# 1DDR3L_16bits.net
KiCad netlist of a schematic drawn in Altium Designer
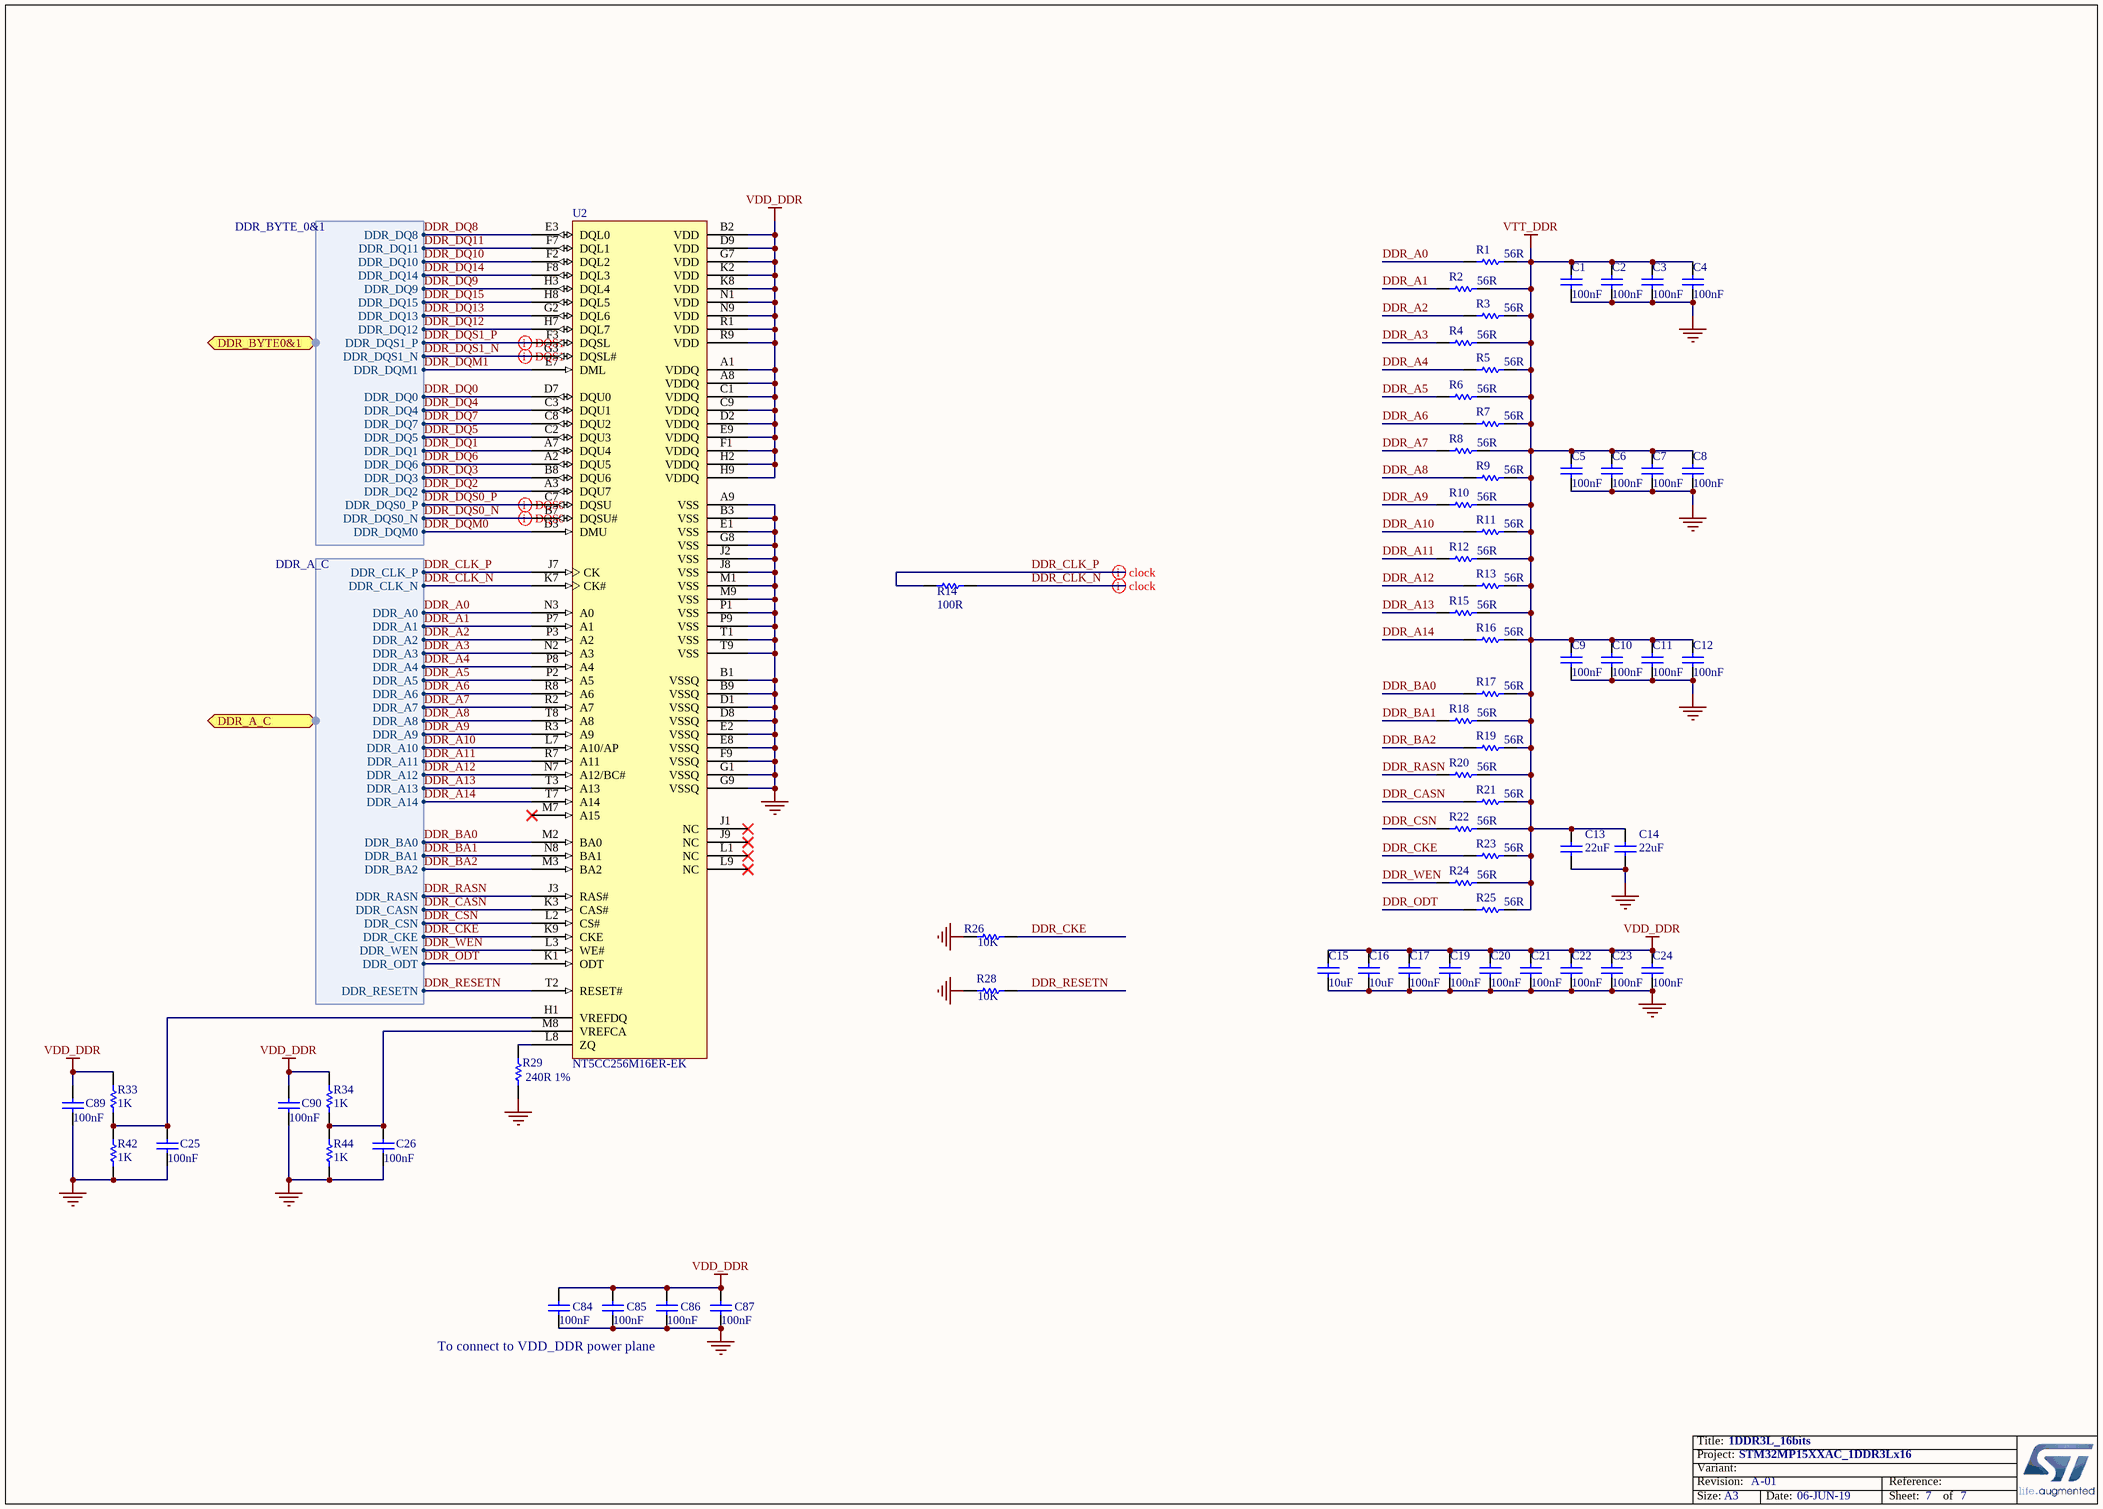
[diagram p0: 1DDR3L_16bits .SchDoc]

(export (version "E")
  (design (tool "Eeschema 10.0.6"))
  (components
    (comp (ref "C1")
      (value "100nF")
      (footprint "C0402")
      (description "Capacitor, MLCC, 100nF, 16V, X7R, 10%, 0402, T=0.5mm")
      (fields
        (field (name "INTERNAL_PART_NUMBER") "MCD-00006")
        (field (name "MANUFACTURER_PART_NUMBER") "CC0402KRX7R7BB104")
        (field (name "PROVIDED_BY") "SUBCO")
      )
      (libsource (lib "MCD_PARTS_database") (part "Capacitor"))
    )
    (comp (ref "C2")
      (value "100nF")
      (footprint "C0402")
      (description "Capacitor, MLCC, 100nF, 16V, X7R, 10%, 0402, T=0.5mm")
      (fields
        (field (name "INTERNAL_PART_NUMBER") "MCD-00006")
        (field (name "MANUFACTURER_PART_NUMBER") "CC0402KRX7R7BB104")
        (field (name "PROVIDED_BY") "SUBCO")
      )
      (libsource (lib "MCD_PARTS_database") (part "Capacitor"))
    )
    (comp (ref "C3")
      (value "100nF")
      (footprint "C0402")
      (description "Capacitor, MLCC, 100nF, 16V, X7R, 10%, 0402, T=0.5mm")
      (fields
        (field (name "INTERNAL_PART_NUMBER") "MCD-00006")
        (field (name "MANUFACTURER_PART_NUMBER") "CC0402KRX7R7BB104")
        (field (name "PROVIDED_BY") "SUBCO")
      )
      (libsource (lib "MCD_PARTS_database") (part "Capacitor"))
    )
    (comp (ref "C4")
      (value "100nF")
      (footprint "C0402")
      (description "Capacitor, MLCC, 100nF, 16V, X7R, 10%, 0402, T=0.5mm")
      (fields
        (field (name "INTERNAL_PART_NUMBER") "MCD-00006")
        (field (name "MANUFACTURER_PART_NUMBER") "CC0402KRX7R7BB104")
        (field (name "PROVIDED_BY") "SUBCO")
      )
      (libsource (lib "MCD_PARTS_database") (part "Capacitor"))
    )
    (comp (ref "C5")
      (value "100nF")
      (footprint "C0402")
      (description "Capacitor, MLCC, 100nF, 16V, X7R, 10%, 0402, T=0.5mm")
      (fields
        (field (name "INTERNAL_PART_NUMBER") "MCD-00006")
        (field (name "MANUFACTURER_PART_NUMBER") "CC0402KRX7R7BB104")
        (field (name "PROVIDED_BY") "SUBCO")
      )
      (libsource (lib "MCD_PARTS_database") (part "Capacitor"))
    )
    (comp (ref "C6")
      (value "100nF")
      (footprint "C0402")
      (description "Capacitor, MLCC, 100nF, 16V, X7R, 10%, 0402, T=0.5mm")
      (fields
        (field (name "INTERNAL_PART_NUMBER") "MCD-00006")
        (field (name "MANUFACTURER_PART_NUMBER") "CC0402KRX7R7BB104")
        (field (name "PROVIDED_BY") "SUBCO")
      )
      (libsource (lib "MCD_PARTS_database") (part "Capacitor"))
    )
    (comp (ref "C7")
      (value "100nF")
      (footprint "C0402")
      (description "Capacitor, MLCC, 100nF, 16V, X7R, 10%, 0402, T=0.5mm")
      (fields
        (field (name "INTERNAL_PART_NUMBER") "MCD-00006")
        (field (name "MANUFACTURER_PART_NUMBER") "CC0402KRX7R7BB104")
        (field (name "PROVIDED_BY") "SUBCO")
      )
      (libsource (lib "MCD_PARTS_database") (part "Capacitor"))
    )
    (comp (ref "C8")
      (value "100nF")
      (footprint "C0402")
      (description "Capacitor, MLCC, 100nF, 16V, X7R, 10%, 0402, T=0.5mm")
      (fields
        (field (name "INTERNAL_PART_NUMBER") "MCD-00006")
        (field (name "MANUFACTURER_PART_NUMBER") "CC0402KRX7R7BB104")
        (field (name "PROVIDED_BY") "SUBCO")
      )
      (libsource (lib "MCD_PARTS_database") (part "Capacitor"))
    )
    (comp (ref "C9")
      (value "100nF")
      (footprint "C0402")
      (description "Capacitor, MLCC, 100nF, 16V, X7R, 10%, 0402, T=0.5mm")
      (fields
        (field (name "INTERNAL_PART_NUMBER") "MCD-00006")
        (field (name "MANUFACTURER_PART_NUMBER") "CC0402KRX7R7BB104")
        (field (name "PROVIDED_BY") "SUBCO")
      )
      (libsource (lib "MCD_PARTS_database") (part "Capacitor"))
    )
    (comp (ref "C10")
      (value "100nF")
      (footprint "C0402")
      (description "Capacitor, MLCC, 100nF, 16V, X7R, 10%, 0402, T=0.5mm")
      (fields
        (field (name "INTERNAL_PART_NUMBER") "MCD-00006")
        (field (name "MANUFACTURER_PART_NUMBER") "CC0402KRX7R7BB104")
        (field (name "PROVIDED_BY") "SUBCO")
      )
      (libsource (lib "MCD_PARTS_database") (part "Capacitor"))
    )
    (comp (ref "C11")
      (value "100nF")
      (footprint "C0402")
      (description "Capacitor, MLCC, 100nF, 16V, X7R, 10%, 0402, T=0.5mm")
      (fields
        (field (name "INTERNAL_PART_NUMBER") "MCD-00006")
        (field (name "MANUFACTURER_PART_NUMBER") "CC0402KRX7R7BB104")
        (field (name "PROVIDED_BY") "SUBCO")
      )
      (libsource (lib "MCD_PARTS_database") (part "Capacitor"))
    )
    (comp (ref "C12")
      (value "100nF")
      (footprint "C0402")
      (description "Capacitor, MLCC, 100nF, 16V, X7R, 10%, 0402, T=0.5mm")
      (fields
        (field (name "INTERNAL_PART_NUMBER") "MCD-00006")
        (field (name "MANUFACTURER_PART_NUMBER") "CC0402KRX7R7BB104")
        (field (name "PROVIDED_BY") "SUBCO")
      )
      (libsource (lib "MCD_PARTS_database") (part "Capacitor"))
    )
    (comp (ref "C13")
      (value "22uF")
      (footprint "C0603")
      (description "Capacitor, MLCC, 22uF, 6V3, X5R, 20%, 0603, T=0,8mm")
      (fields
        (field (name "INTERNAL_PART_NUMBER") "MCD-00100")
        (field (name "MANUFACTURER_PART_NUMBER") "GRM188R60J226MEA0J")
        (field (name "PROVIDED_BY") "SUBCO")
      )
      (libsource (lib "MCD_PARTS_database") (part "Capacitor"))
    )
    (comp (ref "C14")
      (value "22uF")
      (footprint "C0603")
      (description "Capacitor, MLCC, 22uF, 6V3, X5R, 20%, 0603, T=0,8mm")
      (fields
        (field (name "INTERNAL_PART_NUMBER") "MCD-00100")
        (field (name "MANUFACTURER_PART_NUMBER") "GRM188R60J226MEA0J")
        (field (name "PROVIDED_BY") "SUBCO")
      )
      (libsource (lib "MCD_PARTS_database") (part "Capacitor"))
    )
    (comp (ref "C15")
      (value "10uF")
      (footprint "C0603")
      (description "Capacitor, MLCC, 10uF, 10V, X5R, 10%, 0603, T=0.8mm")
      (fields
        (field (name "INTERNAL_PART_NUMBER") "MCD-01124")
        (field (name "MANUFACTURER_PART_NUMBER") "GRM188R61A106KAAL")
        (field (name "PROVIDED_BY") "SUBCO")
      )
      (libsource (lib "MCD_PARTS_database") (part "Capacitor"))
    )
    (comp (ref "C16")
      (value "10uF")
      (footprint "C0603")
      (description "Capacitor, MLCC, 10uF, 10V, X5R, 10%, 0603, T=0.8mm")
      (fields
        (field (name "INTERNAL_PART_NUMBER") "MCD-01124")
        (field (name "MANUFACTURER_PART_NUMBER") "GRM188R61A106KAAL")
        (field (name "PROVIDED_BY") "SUBCO")
      )
      (libsource (lib "MCD_PARTS_database") (part "Capacitor"))
    )
    (comp (ref "C17")
      (value "100nF")
      (footprint "C0402")
      (description "Capacitor, MLCC, 100nF, 16V, X7R, 10%, 0402, T=0.5mm")
      (fields
        (field (name "INTERNAL_PART_NUMBER") "MCD-00006")
        (field (name "MANUFACTURER_PART_NUMBER") "CC0402KRX7R7BB104")
        (field (name "PROVIDED_BY") "SUBCO")
      )
      (libsource (lib "MCD_PARTS_database") (part "Capacitor"))
    )
    (comp (ref "C19")
      (value "100nF")
      (footprint "C0402")
      (description "Capacitor, MLCC, 100nF, 16V, X7R, 10%, 0402, T=0.5mm")
      (fields
        (field (name "INTERNAL_PART_NUMBER") "MCD-00006")
        (field (name "MANUFACTURER_PART_NUMBER") "CC0402KRX7R7BB104")
        (field (name "PROVIDED_BY") "SUBCO")
      )
      (libsource (lib "MCD_PARTS_database") (part "Capacitor"))
    )
    (comp (ref "C20")
      (value "100nF")
      (footprint "C0402")
      (description "Capacitor, MLCC, 100nF, 16V, X7R, 10%, 0402, T=0.5mm")
      (fields
        (field (name "INTERNAL_PART_NUMBER") "MCD-00006")
        (field (name "MANUFACTURER_PART_NUMBER") "CC0402KRX7R7BB104")
        (field (name "PROVIDED_BY") "SUBCO")
      )
      (libsource (lib "MCD_PARTS_database") (part "Capacitor"))
    )
    (comp (ref "C21")
      (value "100nF")
      (footprint "C0402")
      (description "Capacitor, MLCC, 100nF, 16V, X7R, 10%, 0402, T=0.5mm")
      (fields
        (field (name "INTERNAL_PART_NUMBER") "MCD-00006")
        (field (name "MANUFACTURER_PART_NUMBER") "CC0402KRX7R7BB104")
        (field (name "PROVIDED_BY") "SUBCO")
      )
      (libsource (lib "MCD_PARTS_database") (part "Capacitor"))
    )
    (comp (ref "C22")
      (value "100nF")
      (footprint "C0402")
      (description "Capacitor, MLCC, 100nF, 16V, X7R, 10%, 0402, T=0.5mm")
      (fields
        (field (name "INTERNAL_PART_NUMBER") "MCD-00006")
        (field (name "MANUFACTURER_PART_NUMBER") "CC0402KRX7R7BB104")
        (field (name "PROVIDED_BY") "SUBCO")
      )
      (libsource (lib "MCD_PARTS_database") (part "Capacitor"))
    )
    (comp (ref "C23")
      (value "100nF")
      (footprint "C0402")
      (description "Capacitor, MLCC, 100nF, 16V, X7R, 10%, 0402, T=0.5mm")
      (fields
        (field (name "INTERNAL_PART_NUMBER") "MCD-00006")
        (field (name "MANUFACTURER_PART_NUMBER") "CC0402KRX7R7BB104")
        (field (name "PROVIDED_BY") "SUBCO")
      )
      (libsource (lib "MCD_PARTS_database") (part "Capacitor"))
    )
    (comp (ref "C24")
      (value "100nF")
      (footprint "C0402")
      (description "Capacitor, MLCC, 100nF, 16V, X7R, 10%, 0402, T=0.5mm")
      (fields
        (field (name "INTERNAL_PART_NUMBER") "MCD-00006")
        (field (name "MANUFACTURER_PART_NUMBER") "CC0402KRX7R7BB104")
        (field (name "PROVIDED_BY") "SUBCO")
      )
      (libsource (lib "MCD_PARTS_database") (part "Capacitor"))
    )
    (comp (ref "C25")
      (value "100nF")
      (footprint "C0402")
      (description "Capacitor, MLCC, 100nF, 16V, X7R, 10%, 0402, T=0.5mm")
      (fields
        (field (name "INTERNAL_PART_NUMBER") "MCD-00006")
        (field (name "MANUFACTURER_PART_NUMBER") "CC0402KRX7R7BB104")
        (field (name "PROVIDED_BY") "SUBCO")
      )
      (libsource (lib "MCD_PARTS_database") (part "Capacitor"))
    )
    (comp (ref "C26")
      (value "100nF")
      (footprint "C0402")
      (description "Capacitor, MLCC, 100nF, 16V, X7R, 10%, 0402, T=0.5mm")
      (fields
        (field (name "INTERNAL_PART_NUMBER") "MCD-00006")
        (field (name "MANUFACTURER_PART_NUMBER") "CC0402KRX7R7BB104")
        (field (name "PROVIDED_BY") "SUBCO")
      )
      (libsource (lib "MCD_PARTS_database") (part "Capacitor"))
    )
    (comp (ref "C84")
      (value "100nF")
      (footprint "C0402")
      (description "Capacitor, MLCC, 100nF, 16V, X7R, 10%, 0402, T=0.5mm")
      (fields
        (field (name "INTERNAL_PART_NUMBER") "MCD-00006")
        (field (name "MANUFACTURER_PART_NUMBER") "CC0402KRX7R7BB104")
        (field (name "PROVIDED_BY") "SUBCO")
      )
      (libsource (lib "MCD_PARTS_database") (part "Capacitor"))
    )
    (comp (ref "C85")
      (value "100nF")
      (footprint "C0402")
      (description "Capacitor, MLCC, 100nF, 16V, X7R, 10%, 0402, T=0.5mm")
      (fields
        (field (name "INTERNAL_PART_NUMBER") "MCD-00006")
        (field (name "MANUFACTURER_PART_NUMBER") "CC0402KRX7R7BB104")
        (field (name "PROVIDED_BY") "SUBCO")
      )
      (libsource (lib "MCD_PARTS_database") (part "Capacitor"))
    )
    (comp (ref "C86")
      (value "100nF")
      (footprint "C0402")
      (description "Capacitor, MLCC, 100nF, 16V, X7R, 10%, 0402, T=0.5mm")
      (fields
        (field (name "INTERNAL_PART_NUMBER") "MCD-00006")
        (field (name "MANUFACTURER_PART_NUMBER") "CC0402KRX7R7BB104")
        (field (name "PROVIDED_BY") "SUBCO")
      )
      (libsource (lib "MCD_PARTS_database") (part "Capacitor"))
    )
    (comp (ref "C87")
      (value "100nF")
      (footprint "C0402")
      (description "Capacitor, MLCC, 100nF, 16V, X7R, 10%, 0402, T=0.5mm")
      (fields
        (field (name "INTERNAL_PART_NUMBER") "MCD-00006")
        (field (name "MANUFACTURER_PART_NUMBER") "CC0402KRX7R7BB104")
        (field (name "PROVIDED_BY") "SUBCO")
      )
      (libsource (lib "MCD_PARTS_database") (part "Capacitor"))
    )
    (comp (ref "C89")
      (value "100nF")
      (footprint "C0402")
      (description "Capacitor, MLCC, 100nF, 16V, X7R, 10%, 0402, T=0.5mm")
      (fields
        (field (name "INTERNAL_PART_NUMBER") "MCD-00006")
        (field (name "MANUFACTURER_PART_NUMBER") "CC0402KRX7R7BB104")
        (field (name "PROVIDED_BY") "SUBCO")
      )
      (libsource (lib "MCD_PARTS_database") (part "Capacitor"))
    )
    (comp (ref "C90")
      (value "100nF")
      (footprint "C0402")
      (description "Capacitor, MLCC, 100nF, 16V, X7R, 10%, 0402, T=0.5mm")
      (fields
        (field (name "INTERNAL_PART_NUMBER") "MCD-00006")
        (field (name "MANUFACTURER_PART_NUMBER") "CC0402KRX7R7BB104")
        (field (name "PROVIDED_BY") "SUBCO")
      )
      (libsource (lib "MCD_PARTS_database") (part "Capacitor"))
    )
    (comp (ref "R1")
      (value "56R")
      (footprint "R0402")
      (description "Resistor,56R,0402,1%,1/16W")
      (fields
        (field (name "INTERNAL_PART_NUMBER") "MCD-00054")
        (field (name "MANUFACTURER_PART_NUMBER") "RC0402FR-0756RL")
        (field (name "PROVIDED_BY") "SUBCO")
      )
      (libsource (lib "MCD_PARTS_database") (part "Resistor"))
    )
    (comp (ref "R2")
      (value "56R")
      (footprint "R0402")
      (description "Resistor,56R,0402,1%,1/16W")
      (fields
        (field (name "INTERNAL_PART_NUMBER") "MCD-00054")
        (field (name "MANUFACTURER_PART_NUMBER") "RC0402FR-0756RL")
        (field (name "PROVIDED_BY") "SUBCO")
      )
      (libsource (lib "MCD_PARTS_database") (part "Resistor"))
    )
    (comp (ref "R3")
      (value "56R")
      (footprint "R0402")
      (description "Resistor,56R,0402,1%,1/16W")
      (fields
        (field (name "INTERNAL_PART_NUMBER") "MCD-00054")
        (field (name "MANUFACTURER_PART_NUMBER") "RC0402FR-0756RL")
        (field (name "PROVIDED_BY") "SUBCO")
      )
      (libsource (lib "MCD_PARTS_database") (part "Resistor"))
    )
    (comp (ref "R4")
      (value "56R")
      (footprint "R0402")
      (description "Resistor,56R,0402,1%,1/16W")
      (fields
        (field (name "INTERNAL_PART_NUMBER") "MCD-00054")
        (field (name "MANUFACTURER_PART_NUMBER") "RC0402FR-0756RL")
        (field (name "PROVIDED_BY") "SUBCO")
      )
      (libsource (lib "MCD_PARTS_database") (part "Resistor"))
    )
    (comp (ref "R5")
      (value "56R")
      (footprint "R0402")
      (description "Resistor,56R,0402,1%,1/16W")
      (fields
        (field (name "INTERNAL_PART_NUMBER") "MCD-00054")
        (field (name "MANUFACTURER_PART_NUMBER") "RC0402FR-0756RL")
        (field (name "PROVIDED_BY") "SUBCO")
      )
      (libsource (lib "MCD_PARTS_database") (part "Resistor"))
    )
    (comp (ref "R6")
      (value "56R")
      (footprint "R0402")
      (description "Resistor,56R,0402,1%,1/16W")
      (fields
        (field (name "INTERNAL_PART_NUMBER") "MCD-00054")
        (field (name "MANUFACTURER_PART_NUMBER") "RC0402FR-0756RL")
        (field (name "PROVIDED_BY") "SUBCO")
      )
      (libsource (lib "MCD_PARTS_database") (part "Resistor"))
    )
    (comp (ref "R7")
      (value "56R")
      (footprint "R0402")
      (description "Resistor,56R,0402,1%,1/16W")
      (fields
        (field (name "INTERNAL_PART_NUMBER") "MCD-00054")
        (field (name "MANUFACTURER_PART_NUMBER") "RC0402FR-0756RL")
        (field (name "PROVIDED_BY") "SUBCO")
      )
      (libsource (lib "MCD_PARTS_database") (part "Resistor"))
    )
    (comp (ref "R8")
      (value "56R")
      (footprint "R0402")
      (description "Resistor,56R,0402,1%,1/16W")
      (fields
        (field (name "INTERNAL_PART_NUMBER") "MCD-00054")
        (field (name "MANUFACTURER_PART_NUMBER") "RC0402FR-0756RL")
        (field (name "PROVIDED_BY") "SUBCO")
      )
      (libsource (lib "MCD_PARTS_database") (part "Resistor"))
    )
    (comp (ref "R9")
      (value "56R")
      (footprint "R0402")
      (description "Resistor,56R,0402,1%,1/16W")
      (fields
        (field (name "INTERNAL_PART_NUMBER") "MCD-00054")
        (field (name "MANUFACTURER_PART_NUMBER") "RC0402FR-0756RL")
        (field (name "PROVIDED_BY") "SUBCO")
      )
      (libsource (lib "MCD_PARTS_database") (part "Resistor"))
    )
    (comp (ref "R10")
      (value "56R")
      (footprint "R0402")
      (description "Resistor,56R,0402,1%,1/16W")
      (fields
        (field (name "INTERNAL_PART_NUMBER") "MCD-00054")
        (field (name "MANUFACTURER_PART_NUMBER") "RC0402FR-0756RL")
        (field (name "PROVIDED_BY") "SUBCO")
      )
      (libsource (lib "MCD_PARTS_database") (part "Resistor"))
    )
    (comp (ref "R11")
      (value "56R")
      (footprint "R0402")
      (description "Resistor,56R,0402,1%,1/16W")
      (fields
        (field (name "INTERNAL_PART_NUMBER") "MCD-00054")
        (field (name "MANUFACTURER_PART_NUMBER") "RC0402FR-0756RL")
        (field (name "PROVIDED_BY") "SUBCO")
      )
      (libsource (lib "MCD_PARTS_database") (part "Resistor"))
    )
    (comp (ref "R12")
      (value "56R")
      (footprint "R0402")
      (description "Resistor,56R,0402,1%,1/16W")
      (fields
        (field (name "INTERNAL_PART_NUMBER") "MCD-00054")
        (field (name "MANUFACTURER_PART_NUMBER") "RC0402FR-0756RL")
        (field (name "PROVIDED_BY") "SUBCO")
      )
      (libsource (lib "MCD_PARTS_database") (part "Resistor"))
    )
    (comp (ref "R13")
      (value "56R")
      (footprint "R0402")
      (description "Resistor,56R,0402,1%,1/16W")
      (fields
        (field (name "INTERNAL_PART_NUMBER") "MCD-00054")
        (field (name "MANUFACTURER_PART_NUMBER") "RC0402FR-0756RL")
        (field (name "PROVIDED_BY") "SUBCO")
      )
      (libsource (lib "MCD_PARTS_database") (part "Resistor"))
    )
    (comp (ref "R14")
      (value "100R")
      (footprint "R0402")
      (description "Resistor,100R,0402,1%,1/16W")
      (fields
        (field (name "INTERNAL_PART_NUMBER") "MCD-00067")
        (field (name "MANUFACTURER_PART_NUMBER") "RC0402FR-07100RL")
        (field (name "PROVIDED_BY") "SUBCO")
      )
      (libsource (lib "MCD_PARTS_database") (part "Resistor"))
    )
    (comp (ref "R15")
      (value "56R")
      (footprint "R0402")
      (description "Resistor,56R,0402,1%,1/16W")
      (fields
        (field (name "INTERNAL_PART_NUMBER") "MCD-00054")
        (field (name "MANUFACTURER_PART_NUMBER") "RC0402FR-0756RL")
        (field (name "PROVIDED_BY") "SUBCO")
      )
      (libsource (lib "MCD_PARTS_database") (part "Resistor"))
    )
    (comp (ref "R16")
      (value "56R")
      (footprint "R0402")
      (description "Resistor,56R,0402,1%,1/16W")
      (fields
        (field (name "INTERNAL_PART_NUMBER") "MCD-00054")
        (field (name "MANUFACTURER_PART_NUMBER") "RC0402FR-0756RL")
        (field (name "PROVIDED_BY") "SUBCO")
      )
      (libsource (lib "MCD_PARTS_database") (part "Resistor"))
    )
    (comp (ref "R17")
      (value "56R")
      (footprint "R0402")
      (description "Resistor,56R,0402,1%,1/16W")
      (fields
        (field (name "INTERNAL_PART_NUMBER") "MCD-00054")
        (field (name "MANUFACTURER_PART_NUMBER") "RC0402FR-0756RL")
        (field (name "PROVIDED_BY") "SUBCO")
      )
      (libsource (lib "MCD_PARTS_database") (part "Resistor"))
    )
    (comp (ref "R18")
      (value "56R")
      (footprint "R0402")
      (description "Resistor,56R,0402,1%,1/16W")
      (fields
        (field (name "INTERNAL_PART_NUMBER") "MCD-00054")
        (field (name "MANUFACTURER_PART_NUMBER") "RC0402FR-0756RL")
        (field (name "PROVIDED_BY") "SUBCO")
      )
      (libsource (lib "MCD_PARTS_database") (part "Resistor"))
    )
    (comp (ref "R19")
      (value "56R")
      (footprint "R0402")
      (description "Resistor,56R,0402,1%,1/16W")
      (fields
        (field (name "INTERNAL_PART_NUMBER") "MCD-00054")
        (field (name "MANUFACTURER_PART_NUMBER") "RC0402FR-0756RL")
        (field (name "PROVIDED_BY") "SUBCO")
      )
      (libsource (lib "MCD_PARTS_database") (part "Resistor"))
    )
    (comp (ref "R20")
      (value "56R")
      (footprint "R0402")
      (description "Resistor,56R,0402,1%,1/16W")
      (fields
        (field (name "INTERNAL_PART_NUMBER") "MCD-00054")
        (field (name "MANUFACTURER_PART_NUMBER") "RC0402FR-0756RL")
        (field (name "PROVIDED_BY") "SUBCO")
      )
      (libsource (lib "MCD_PARTS_database") (part "Resistor"))
    )
    (comp (ref "R21")
      (value "56R")
      (footprint "R0402")
      (description "Resistor,56R,0402,1%,1/16W")
      (fields
        (field (name "INTERNAL_PART_NUMBER") "MCD-00054")
        (field (name "MANUFACTURER_PART_NUMBER") "RC0402FR-0756RL")
        (field (name "PROVIDED_BY") "SUBCO")
      )
      (libsource (lib "MCD_PARTS_database") (part "Resistor"))
    )
    (comp (ref "R22")
      (value "56R")
      (footprint "R0402")
      (description "Resistor,56R,0402,1%,1/16W")
      (fields
        (field (name "INTERNAL_PART_NUMBER") "MCD-00054")
        (field (name "MANUFACTURER_PART_NUMBER") "RC0402FR-0756RL")
        (field (name "PROVIDED_BY") "SUBCO")
      )
      (libsource (lib "MCD_PARTS_database") (part "Resistor"))
    )
    (comp (ref "R23")
      (value "56R")
      (footprint "R0402")
      (description "Resistor,56R,0402,1%,1/16W")
      (fields
        (field (name "INTERNAL_PART_NUMBER") "MCD-00054")
        (field (name "MANUFACTURER_PART_NUMBER") "RC0402FR-0756RL")
        (field (name "PROVIDED_BY") "SUBCO")
      )
      (libsource (lib "MCD_PARTS_database") (part "Resistor"))
    )
    (comp (ref "R24")
      (value "56R")
      (footprint "R0402")
      (description "Resistor,56R,0402,1%,1/16W")
      (fields
        (field (name "INTERNAL_PART_NUMBER") "MCD-00054")
        (field (name "MANUFACTURER_PART_NUMBER") "RC0402FR-0756RL")
        (field (name "PROVIDED_BY") "SUBCO")
      )
      (libsource (lib "MCD_PARTS_database") (part "Resistor"))
    )
    (comp (ref "R25")
      (value "56R")
      (footprint "R0402")
      (description "Resistor,56R,0402,1%,1/16W")
      (fields
        (field (name "INTERNAL_PART_NUMBER") "MCD-00054")
        (field (name "MANUFACTURER_PART_NUMBER") "RC0402FR-0756RL")
        (field (name "PROVIDED_BY") "SUBCO")
      )
      (libsource (lib "MCD_PARTS_database") (part "Resistor"))
    )
    (comp (ref "R26")
      (value "10K")
      (footprint "R0402")
      (description "Resistor,10K,0402,1%,1/16W")
      (fields
        (field (name "INTERNAL_PART_NUMBER") "MCD-00053")
        (field (name "MANUFACTURER_PART_NUMBER") "RC0402FR-0710KL")
        (field (name "PROVIDED_BY") "SUBCO")
      )
      (libsource (lib "MCD_PARTS_database") (part "Resistor"))
    )
    (comp (ref "R28")
      (value "10K")
      (footprint "R0402")
      (description "Resistor,10K,0402,1%,1/16W")
      (fields
        (field (name "INTERNAL_PART_NUMBER") "MCD-00053")
        (field (name "MANUFACTURER_PART_NUMBER") "RC0402FR-0710KL")
        (field (name "PROVIDED_BY") "SUBCO")
      )
      (libsource (lib "MCD_PARTS_database") (part "Resistor"))
    )
    (comp (ref "R29")
      (value "240R 1%")
      (footprint "R0402")
      (description "Resistor,240R,0402,1%,1/16W")
      (fields
        (field (name "INTERNAL_PART_NUMBER") "MCD-00120")
        (field (name "MANUFACTURER_PART_NUMBER") "RC0402FR-07240RL")
        (field (name "PROVIDED_BY") "SUBCO")
      )
      (libsource (lib "MCD_PARTS_database") (part "Resistor"))
    )
    (comp (ref "R33")
      (value "1K")
      (footprint "R0402")
      (description "Resistor,1K,0402,1%,1/16W")
      (fields
        (field (name "INTERNAL_PART_NUMBER") "MCD-00061")
        (field (name "MANUFACTURER_PART_NUMBER") "RC0402FR-071KL")
        (field (name "PROVIDED_BY") "SUBCO")
      )
      (libsource (lib "MCD_PARTS_database") (part "Resistor"))
    )
    (comp (ref "R34")
      (value "1K")
      (footprint "R0402")
      (description "Resistor,1K,0402,1%,1/16W")
      (fields
        (field (name "INTERNAL_PART_NUMBER") "MCD-00061")
        (field (name "MANUFACTURER_PART_NUMBER") "RC0402FR-071KL")
        (field (name "PROVIDED_BY") "SUBCO")
      )
      (libsource (lib "MCD_PARTS_database") (part "Resistor"))
    )
    (comp (ref "R42")
      (value "1K")
      (footprint "R0402")
      (description "Resistor,1K,0402,1%,1/16W")
      (fields
        (field (name "INTERNAL_PART_NUMBER") "MCD-00061")
        (field (name "MANUFACTURER_PART_NUMBER") "RC0402FR-071KL")
        (field (name "PROVIDED_BY") "SUBCO")
      )
      (libsource (lib "MCD_PARTS_database") (part "Resistor"))
    )
    (comp (ref "R44")
      (value "1K")
      (footprint "R0402")
      (description "Resistor,1K,0402,1%,1/16W")
      (fields
        (field (name "INTERNAL_PART_NUMBER") "MCD-00061")
        (field (name "MANUFACTURER_PART_NUMBER") "RC0402FR-071KL")
        (field (name "PROVIDED_BY") "SUBCO")
      )
      (libsource (lib "MCD_PARTS_database") (part "Resistor"))
    )
    (comp (ref "U2")
      (value "NT5CC256M16ER-EK")
      (footprint "ICC_VFBGA96_9x13_P080")
      (description "Memory,DDR3L,4Gb,256Mbx16,933Mhz,1V35,TFBGA")
      (fields
        (field (name "INTERNAL_PART_NUMBER") "MCD-01811")
        (field (name "MANUFACTURER") "NANYA")
        (field (name "PROVIDED_BY") "SUBCO")
      )
      (libsource (lib "MCD_PARTS_database") (part "NT5CC256M16ER-EK"))
    )
  )
  (nets
    (net (code "3") (name "/DDR_A0") (class "Default")
      (node (ref "R1") (pin "1") (pinfunction "1_1") (pintype "passive"))
      (node (ref "U2") (pin "N3") (pinfunction "A0_N3") (pintype "input"))
    )
    (net (code "4") (name "/DDR_A1") (class "Default")
      (node (ref "R2") (pin "1") (pinfunction "1_1") (pintype "passive"))
      (node (ref "U2") (pin "P7") (pinfunction "A1_P7") (pintype "input"))
    )
    (net (code "5") (name "/DDR_A2") (class "Default")
      (node (ref "R3") (pin "1") (pinfunction "1_1") (pintype "passive"))
      (node (ref "U2") (pin "P3") (pinfunction "A2_P3") (pintype "input"))
    )
    (net (code "6") (name "/DDR_A3") (class "Default")
      (node (ref "R4") (pin "1") (pinfunction "1_1") (pintype "passive"))
      (node (ref "U2") (pin "N2") (pinfunction "A3_N2") (pintype "input"))
    )
    (net (code "7") (name "/DDR_A4") (class "Default")
      (node (ref "R5") (pin "1") (pinfunction "1_1") (pintype "passive"))
      (node (ref "U2") (pin "P8") (pinfunction "A4_P8") (pintype "input"))
    )
    (net (code "8") (name "/DDR_A5") (class "Default")
      (node (ref "R6") (pin "1") (pinfunction "1_1") (pintype "passive"))
      (node (ref "U2") (pin "P2") (pinfunction "A5_P2") (pintype "input"))
    )
    (net (code "9") (name "/DDR_A6") (class "Default")
      (node (ref "R7") (pin "1") (pinfunction "1_1") (pintype "passive"))
      (node (ref "U2") (pin "R8") (pinfunction "A6_R8") (pintype "input"))
    )
    (net (code "10") (name "/DDR_A7") (class "Default")
      (node (ref "R8") (pin "1") (pinfunction "1_1") (pintype "passive"))
      (node (ref "U2") (pin "R2") (pinfunction "A7_R2") (pintype "input"))
    )
    (net (code "11") (name "/DDR_A8") (class "Default")
      (node (ref "R9") (pin "1") (pinfunction "1_1") (pintype "passive"))
      (node (ref "U2") (pin "T8") (pinfunction "A8_T8") (pintype "input"))
    )
    (net (code "12") (name "/DDR_A9") (class "Default")
      (node (ref "R10") (pin "1") (pinfunction "1_1") (pintype "passive"))
      (node (ref "U2") (pin "R3") (pinfunction "A9_R3") (pintype "input"))
    )
    (net (code "13") (name "/DDR_A10") (class "Default")
      (node (ref "R11") (pin "1") (pinfunction "1_1") (pintype "passive"))
      (node (ref "U2") (pin "L7") (pinfunction "A10/AP_L7") (pintype "input"))
    )
    (net (code "14") (name "/DDR_A11") (class "Default")
      (node (ref "R12") (pin "1") (pinfunction "1_1") (pintype "passive"))
      (node (ref "U2") (pin "R7") (pinfunction "A11_R7") (pintype "input"))
    )
    (net (code "15") (name "/DDR_A12") (class "Default")
      (node (ref "R13") (pin "1") (pinfunction "1_1") (pintype "passive"))
      (node (ref "U2") (pin "N7") (pinfunction "A12/BC#_N7") (pintype "input"))
    )
    (net (code "16") (name "/DDR_A13") (class "Default")
      (node (ref "R15") (pin "1") (pinfunction "1_1") (pintype "passive"))
      (node (ref "U2") (pin "T3") (pinfunction "A13_T3") (pintype "input"))
    )
    (net (code "17") (name "/DDR_A14") (class "Default")
      (node (ref "R16") (pin "1") (pinfunction "1_1") (pintype "passive"))
      (node (ref "U2") (pin "T7") (pinfunction "A14_T7") (pintype "input"))
    )
    (net (code "18") (name "/DDR_BA0") (class "Default")
      (node (ref "R17") (pin "1") (pinfunction "1_1") (pintype "passive"))
      (node (ref "U2") (pin "M2") (pinfunction "BA0_M2") (pintype "input"))
    )
    (net (code "19") (name "/DDR_BA1") (class "Default")
      (node (ref "R18") (pin "1") (pinfunction "1_1") (pintype "passive"))
      (node (ref "U2") (pin "N8") (pinfunction "BA1_N8") (pintype "input"))
    )
    (net (code "20") (name "/DDR_BA2") (class "Default")
      (node (ref "R19") (pin "1") (pinfunction "1_1") (pintype "passive"))
      (node (ref "U2") (pin "M3") (pinfunction "BA2_M3") (pintype "input"))
    )
    (net (code "21") (name "/DDR_CASN") (class "Default")
      (node (ref "R21") (pin "1") (pinfunction "1_1") (pintype "passive"))
      (node (ref "U2") (pin "K3") (pinfunction "CAS#_K3") (pintype "input"))
    )
    (net (code "22") (name "/DDR_CKE") (class "Default")
      (node (ref "R23") (pin "1") (pinfunction "1_1") (pintype "passive"))
      (node (ref "R26") (pin "2") (pinfunction "2_2") (pintype "passive"))
      (node (ref "U2") (pin "K9") (pinfunction "CKE_K9") (pintype "input"))
    )
    (net (code "23") (name "/DDR_CLK_N") (class "Default")
      (node (ref "R14") (pin "2") (pinfunction "2_2") (pintype "passive"))
      (node (ref "U2") (pin "K7") (pinfunction "CK#_K7") (pintype "input"))
    )
    (net (code "24") (name "/DDR_CLK_P") (class "Default")
      (node (ref "R14") (pin "1") (pinfunction "1_1") (pintype "passive"))
      (node (ref "U2") (pin "J7") (pinfunction "CK_J7") (pintype "input"))
    )
    (net (code "25") (name "/DDR_CSN") (class "Default")
      (node (ref "R22") (pin "1") (pinfunction "1_1") (pintype "passive"))
      (node (ref "U2") (pin "L2") (pinfunction "CS#_L2") (pintype "input"))
    )
    (net (code "26") (name "/DDR_DQ0") (class "Default")
      (node (ref "U2") (pin "D7") (pinfunction "DQU0_D7") (pintype "bidirectional"))
    )
    (net (code "27") (name "/DDR_DQ1") (class "Default")
      (node (ref "U2") (pin "A7") (pinfunction "DQU4_A7") (pintype "bidirectional"))
    )
    (net (code "28") (name "/DDR_DQ2") (class "Default")
      (node (ref "U2") (pin "A3") (pinfunction "DQU7_A3") (pintype "bidirectional"))
    )
    (net (code "29") (name "/DDR_DQ3") (class "Default")
      (node (ref "U2") (pin "B8") (pinfunction "DQU6_B8") (pintype "bidirectional"))
    )
    (net (code "30") (name "/DDR_DQ4") (class "Default")
      (node (ref "U2") (pin "C3") (pinfunction "DQU1_C3") (pintype "bidirectional"))
    )
    (net (code "31") (name "/DDR_DQ5") (class "Default")
      (node (ref "U2") (pin "C2") (pinfunction "DQU3_C2") (pintype "bidirectional"))
    )
    (net (code "32") (name "/DDR_DQ6") (class "Default")
      (node (ref "U2") (pin "A2") (pinfunction "DQU5_A2") (pintype "bidirectional"))
    )
    (net (code "33") (name "/DDR_DQ7") (class "Default")
      (node (ref "U2") (pin "C8") (pinfunction "DQU2_C8") (pintype "bidirectional"))
    )
    (net (code "34") (name "/DDR_DQ8") (class "Default")
      (node (ref "U2") (pin "E3") (pinfunction "DQL0_E3") (pintype "bidirectional"))
    )
    (net (code "35") (name "/DDR_DQ9") (class "Default")
      (node (ref "U2") (pin "H3") (pinfunction "DQL4_H3") (pintype "bidirectional"))
    )
    (net (code "36") (name "/DDR_DQ10") (class "Default")
      (node (ref "U2") (pin "F2") (pinfunction "DQL2_F2") (pintype "bidirectional"))
    )
    (net (code "37") (name "/DDR_DQ11") (class "Default")
      (node (ref "U2") (pin "F7") (pinfunction "DQL1_F7") (pintype "bidirectional"))
    )
    (net (code "38") (name "/DDR_DQ12") (class "Default")
      (node (ref "U2") (pin "H7") (pinfunction "DQL7_H7") (pintype "bidirectional"))
    )
    (net (code "39") (name "/DDR_DQ13") (class "Default")
      (node (ref "U2") (pin "G2") (pinfunction "DQL6_G2") (pintype "bidirectional"))
    )
    (net (code "40") (name "/DDR_DQ14") (class "Default")
      (node (ref "U2") (pin "F8") (pinfunction "DQL3_F8") (pintype "bidirectional"))
    )
    (net (code "41") (name "/DDR_DQ15") (class "Default")
      (node (ref "U2") (pin "H8") (pinfunction "DQL5_H8") (pintype "bidirectional"))
    )
    (net (code "42") (name "/DDR_DQM0") (class "Default")
      (node (ref "U2") (pin "D3") (pinfunction "DMU_D3") (pintype "input"))
    )
    (net (code "43") (name "/DDR_DQM1") (class "Default")
      (node (ref "U2") (pin "E7") (pinfunction "DML_E7") (pintype "input"))
    )
    (net (code "44") (name "/DDR_DQS0_N") (class "Default")
      (node (ref "U2") (pin "B7") (pinfunction "DQSU#_B7") (pintype "bidirectional"))
    )
    (net (code "45") (name "/DDR_DQS0_P") (class "Default")
      (node (ref "U2") (pin "C7") (pinfunction "DQSU_C7") (pintype "bidirectional"))
    )
    (net (code "46") (name "/DDR_DQS1_N") (class "Default")
      (node (ref "U2") (pin "G3") (pinfunction "DQSL#_G3") (pintype "bidirectional"))
    )
    (net (code "47") (name "/DDR_DQS1_P") (class "Default")
      (node (ref "U2") (pin "F3") (pinfunction "DQSL_F3") (pintype "bidirectional"))
    )
    (net (code "48") (name "/DDR_ODT") (class "Default")
      (node (ref "R25") (pin "1") (pinfunction "1_1") (pintype "passive"))
      (node (ref "U2") (pin "K1") (pinfunction "ODT_K1") (pintype "input"))
    )
    (net (code "49") (name "/DDR_RASN") (class "Default")
      (node (ref "R20") (pin "1") (pinfunction "1_1") (pintype "passive"))
      (node (ref "U2") (pin "J3") (pinfunction "RAS#_J3") (pintype "input"))
    )
    (net (code "50") (name "/DDR_RESETN") (class "Default")
      (node (ref "R28") (pin "2") (pinfunction "2_2") (pintype "passive"))
      (node (ref "U2") (pin "T2") (pinfunction "RESET#_T2") (pintype "input"))
    )
    (net (code "51") (name "/DDR_WEN") (class "Default")
      (node (ref "R24") (pin "1") (pinfunction "1_1") (pintype "passive"))
      (node (ref "U2") (pin "L3") (pinfunction "WE#_L3") (pintype "input"))
    )
    (net (code "54") (name "GND") (class "Default")
      (node (ref "C1") (pin "2") (pinfunction "2_2") (pintype "passive"))
      (node (ref "C10") (pin "2") (pinfunction "2_2") (pintype "passive"))
      (node (ref "C11") (pin "2") (pinfunction "2_2") (pintype "passive"))
      (node (ref "C12") (pin "2") (pinfunction "2_2") (pintype "passive"))
      (node (ref "C13") (pin "1") (pinfunction "1_1") (pintype "passive"))
      (node (ref "C14") (pin "1") (pinfunction "1_1") (pintype "passive"))
      (node (ref "C15") (pin "1") (pinfunction "1_1") (pintype "passive"))
      (node (ref "C16") (pin "1") (pinfunction "1_1") (pintype "passive"))
      (node (ref "C17") (pin "2") (pinfunction "2_2") (pintype "passive"))
      (node (ref "C19") (pin "2") (pinfunction "2_2") (pintype "passive"))
      (node (ref "C2") (pin "2") (pinfunction "2_2") (pintype "passive"))
      (node (ref "C20") (pin "2") (pinfunction "2_2") (pintype "passive"))
      (node (ref "C21") (pin "2") (pinfunction "2_2") (pintype "passive"))
      (node (ref "C22") (pin "2") (pinfunction "2_2") (pintype "passive"))
      (node (ref "C23") (pin "2") (pinfunction "2_2") (pintype "passive"))
      (node (ref "C24") (pin "2") (pinfunction "2_2") (pintype "passive"))
      (node (ref "C25") (pin "2") (pinfunction "2_2") (pintype "passive"))
      (node (ref "C26") (pin "2") (pinfunction "2_2") (pintype "passive"))
      (node (ref "C3") (pin "2") (pinfunction "2_2") (pintype "passive"))
      (node (ref "C4") (pin "2") (pinfunction "2_2") (pintype "passive"))
      (node (ref "C5") (pin "2") (pinfunction "2_2") (pintype "passive"))
      (node (ref "C6") (pin "2") (pinfunction "2_2") (pintype "passive"))
      (node (ref "C7") (pin "2") (pinfunction "2_2") (pintype "passive"))
      (node (ref "C8") (pin "2") (pinfunction "2_2") (pintype "passive"))
      (node (ref "C84") (pin "2") (pinfunction "2_2") (pintype "passive"))
      (node (ref "C85") (pin "2") (pinfunction "2_2") (pintype "passive"))
      (node (ref "C86") (pin "2") (pinfunction "2_2") (pintype "passive"))
      (node (ref "C87") (pin "2") (pinfunction "2_2") (pintype "passive"))
      (node (ref "C89") (pin "2") (pinfunction "2_2") (pintype "passive"))
      (node (ref "C9") (pin "2") (pinfunction "2_2") (pintype "passive"))
      (node (ref "C90") (pin "2") (pinfunction "2_2") (pintype "passive"))
      (node (ref "R26") (pin "1") (pinfunction "1_1") (pintype "passive"))
      (node (ref "R28") (pin "1") (pinfunction "1_1") (pintype "passive"))
      (node (ref "R29") (pin "1") (pinfunction "1_1") (pintype "passive"))
      (node (ref "R42") (pin "1") (pinfunction "1_1") (pintype "passive"))
      (node (ref "R44") (pin "1") (pinfunction "1_1") (pintype "passive"))
      (node (ref "U2") (pin "A9") (pinfunction "VSS_A9") (pintype "power_in"))
      (node (ref "U2") (pin "B1") (pinfunction "VSSQ_B1") (pintype "power_in"))
      (node (ref "U2") (pin "B3") (pinfunction "VSS_B3") (pintype "power_in"))
      (node (ref "U2") (pin "B9") (pinfunction "VSSQ_B9") (pintype "power_in"))
      (node (ref "U2") (pin "D1") (pinfunction "VSSQ_D1") (pintype "power_in"))
      (node (ref "U2") (pin "D8") (pinfunction "VSSQ_D8") (pintype "power_in"))
      (node (ref "U2") (pin "E1") (pinfunction "VSS_E1") (pintype "power_in"))
      (node (ref "U2") (pin "E2") (pinfunction "VSSQ_E2") (pintype "power_in"))
      (node (ref "U2") (pin "E8") (pinfunction "VSSQ_E8") (pintype "power_in"))
      (node (ref "U2") (pin "F9") (pinfunction "VSSQ_F9") (pintype "power_in"))
      (node (ref "U2") (pin "G1") (pinfunction "VSSQ_G1") (pintype "power_in"))
      (node (ref "U2") (pin "G8") (pinfunction "VSS_G8") (pintype "power_in"))
      (node (ref "U2") (pin "G9") (pinfunction "VSSQ_G9") (pintype "power_in"))
      (node (ref "U2") (pin "J2") (pinfunction "VSS_J2") (pintype "power_in"))
      (node (ref "U2") (pin "J8") (pinfunction "VSS_J8") (pintype "power_in"))
      (node (ref "U2") (pin "M1") (pinfunction "VSS_M1") (pintype "power_in"))
      (node (ref "U2") (pin "M9") (pinfunction "VSS_M9") (pintype "power_in"))
      (node (ref "U2") (pin "P1") (pinfunction "VSS_P1") (pintype "power_in"))
      (node (ref "U2") (pin "P9") (pinfunction "VSS_P9") (pintype "power_in"))
      (node (ref "U2") (pin "T1") (pinfunction "VSS_T1") (pintype "power_in"))
      (node (ref "U2") (pin "T9") (pinfunction "VSS_T9") (pintype "power_in"))
    )
    (net (code "55") (name "Net-(U2-VREFCA)") (class "Default")
      (node (ref "C26") (pin "1") (pinfunction "1_1") (pintype "passive"))
      (node (ref "R34") (pin "1") (pinfunction "1_1") (pintype "passive"))
      (node (ref "R44") (pin "2") (pinfunction "2_2") (pintype "passive"))
      (node (ref "U2") (pin "M8") (pinfunction "VREFCA_M8") (pintype "passive"))
    )
    (net (code "56") (name "Net-(U2-VREFDQ)") (class "Default")
      (node (ref "C25") (pin "1") (pinfunction "1_1") (pintype "passive"))
      (node (ref "R33") (pin "1") (pinfunction "1_1") (pintype "passive"))
      (node (ref "R42") (pin "2") (pinfunction "2_2") (pintype "passive"))
      (node (ref "U2") (pin "H1") (pinfunction "VREFDQ_H1") (pintype "passive"))
    )
    (net (code "57") (name "Net-(U2-ZQ)") (class "Default")
      (node (ref "R29") (pin "2") (pinfunction "2_2") (pintype "passive"))
      (node (ref "U2") (pin "L8") (pinfunction "ZQ_L8") (pintype "passive"))
    )
    (net (code "58") (name "VDD_DDR") (class "Default")
      (node (ref "C15") (pin "2") (pinfunction "2_2") (pintype "passive"))
      (node (ref "C16") (pin "2") (pinfunction "2_2") (pintype "passive"))
      (node (ref "C17") (pin "1") (pinfunction "1_1") (pintype "passive"))
      (node (ref "C19") (pin "1") (pinfunction "1_1") (pintype "passive"))
      (node (ref "C20") (pin "1") (pinfunction "1_1") (pintype "passive"))
      (node (ref "C21") (pin "1") (pinfunction "1_1") (pintype "passive"))
      (node (ref "C22") (pin "1") (pinfunction "1_1") (pintype "passive"))
      (node (ref "C23") (pin "1") (pinfunction "1_1") (pintype "passive"))
      (node (ref "C24") (pin "1") (pinfunction "1_1") (pintype "passive"))
      (node (ref "C84") (pin "1") (pinfunction "1_1") (pintype "passive"))
      (node (ref "C85") (pin "1") (pinfunction "1_1") (pintype "passive"))
      (node (ref "C86") (pin "1") (pinfunction "1_1") (pintype "passive"))
      (node (ref "C87") (pin "1") (pinfunction "1_1") (pintype "passive"))
      (node (ref "C89") (pin "1") (pinfunction "1_1") (pintype "passive"))
      (node (ref "C90") (pin "1") (pinfunction "1_1") (pintype "passive"))
      (node (ref "R33") (pin "2") (pinfunction "2_2") (pintype "passive"))
      (node (ref "R34") (pin "2") (pinfunction "2_2") (pintype "passive"))
      (node (ref "U2") (pin "A1") (pinfunction "VDDQ_A1") (pintype "power_in"))
      (node (ref "U2") (pin "A8") (pinfunction "VDDQ_A8") (pintype "power_in"))
      (node (ref "U2") (pin "B2") (pinfunction "VDD_B2") (pintype "power_in"))
      (node (ref "U2") (pin "C1") (pinfunction "VDDQ_C1") (pintype "power_in"))
      (node (ref "U2") (pin "C9") (pinfunction "VDDQ_C9") (pintype "power_in"))
      (node (ref "U2") (pin "D2") (pinfunction "VDDQ_D2") (pintype "power_in"))
      (node (ref "U2") (pin "D9") (pinfunction "VDD_D9") (pintype "power_in"))
      (node (ref "U2") (pin "E9") (pinfunction "VDDQ_E9") (pintype "power_in"))
      (node (ref "U2") (pin "F1") (pinfunction "VDDQ_F1") (pintype "power_in"))
      (node (ref "U2") (pin "G7") (pinfunction "VDD_G7") (pintype "power_in"))
      (node (ref "U2") (pin "H2") (pinfunction "VDDQ_H2") (pintype "power_in"))
      (node (ref "U2") (pin "H9") (pinfunction "VDDQ_H9") (pintype "power_in"))
      (node (ref "U2") (pin "K2") (pinfunction "VDD_K2") (pintype "power_in"))
      (node (ref "U2") (pin "K8") (pinfunction "VDD_K8") (pintype "power_in"))
      (node (ref "U2") (pin "N1") (pinfunction "VDD_N1") (pintype "power_in"))
      (node (ref "U2") (pin "N9") (pinfunction "VDD_N9") (pintype "power_in"))
      (node (ref "U2") (pin "R1") (pinfunction "VDD_R1") (pintype "power_in"))
      (node (ref "U2") (pin "R9") (pinfunction "VDD_R9") (pintype "power_in"))
    )
    (net (code "59") (name "VTT_DDR") (class "Default")
      (node (ref "C1") (pin "1") (pinfunction "1_1") (pintype "passive"))
      (node (ref "C10") (pin "1") (pinfunction "1_1") (pintype "passive"))
      (node (ref "C11") (pin "1") (pinfunction "1_1") (pintype "passive"))
      (node (ref "C12") (pin "1") (pinfunction "1_1") (pintype "passive"))
      (node (ref "C13") (pin "2") (pinfunction "2_2") (pintype "passive"))
      (node (ref "C14") (pin "2") (pinfunction "2_2") (pintype "passive"))
      (node (ref "C2") (pin "1") (pinfunction "1_1") (pintype "passive"))
      (node (ref "C3") (pin "1") (pinfunction "1_1") (pintype "passive"))
      (node (ref "C4") (pin "1") (pinfunction "1_1") (pintype "passive"))
      (node (ref "C5") (pin "1") (pinfunction "1_1") (pintype "passive"))
      (node (ref "C6") (pin "1") (pinfunction "1_1") (pintype "passive"))
      (node (ref "C7") (pin "1") (pinfunction "1_1") (pintype "passive"))
      (node (ref "C8") (pin "1") (pinfunction "1_1") (pintype "passive"))
      (node (ref "C9") (pin "1") (pinfunction "1_1") (pintype "passive"))
      (node (ref "R1") (pin "2") (pinfunction "2_2") (pintype "passive"))
      (node (ref "R10") (pin "2") (pinfunction "2_2") (pintype "passive"))
      (node (ref "R11") (pin "2") (pinfunction "2_2") (pintype "passive"))
      (node (ref "R12") (pin "2") (pinfunction "2_2") (pintype "passive"))
      (node (ref "R13") (pin "2") (pinfunction "2_2") (pintype "passive"))
      (node (ref "R15") (pin "2") (pinfunction "2_2") (pintype "passive"))
      (node (ref "R16") (pin "2") (pinfunction "2_2") (pintype "passive"))
      (node (ref "R17") (pin "2") (pinfunction "2_2") (pintype "passive"))
      (node (ref "R18") (pin "2") (pinfunction "2_2") (pintype "passive"))
      (node (ref "R19") (pin "2") (pinfunction "2_2") (pintype "passive"))
      (node (ref "R2") (pin "2") (pinfunction "2_2") (pintype "passive"))
      (node (ref "R20") (pin "2") (pinfunction "2_2") (pintype "passive"))
      (node (ref "R21") (pin "2") (pinfunction "2_2") (pintype "passive"))
      (node (ref "R22") (pin "2") (pinfunction "2_2") (pintype "passive"))
      (node (ref "R23") (pin "2") (pinfunction "2_2") (pintype "passive"))
      (node (ref "R24") (pin "2") (pinfunction "2_2") (pintype "passive"))
      (node (ref "R25") (pin "2") (pinfunction "2_2") (pintype "passive"))
      (node (ref "R3") (pin "2") (pinfunction "2_2") (pintype "passive"))
      (node (ref "R4") (pin "2") (pinfunction "2_2") (pintype "passive"))
      (node (ref "R5") (pin "2") (pinfunction "2_2") (pintype "passive"))
      (node (ref "R6") (pin "2") (pinfunction "2_2") (pintype "passive"))
      (node (ref "R7") (pin "2") (pinfunction "2_2") (pintype "passive"))
      (node (ref "R8") (pin "2") (pinfunction "2_2") (pintype "passive"))
      (node (ref "R9") (pin "2") (pinfunction "2_2") (pintype "passive"))
    )
    (net (code "60") (name "unconnected-(U2-A15-PadM7)") (class "Default")
      (node (ref "U2") (pin "M7") (pinfunction "A15_M7") (pintype "input+no_connect"))
    )
    (net (code "61") (name "unconnected-(U2-NC-PadJ1)") (class "Default")
      (node (ref "U2") (pin "J1") (pinfunction "NC_J1") (pintype "passive+no_connect"))
    )
    (net (code "62") (name "unconnected-(U2-NC-PadJ9)") (class "Default")
      (node (ref "U2") (pin "J9") (pinfunction "NC_J9") (pintype "passive+no_connect"))
    )
    (net (code "63") (name "unconnected-(U2-NC-PadL1)") (class "Default")
      (node (ref "U2") (pin "L1") (pinfunction "NC_L1") (pintype "passive+no_connect"))
    )
    (net (code "64") (name "unconnected-(U2-NC-PadL9)") (class "Default")
      (node (ref "U2") (pin "L9") (pinfunction "NC_L9") (pintype "passive+no_connect"))
    )
  )
)
